# Project_Tsc_v40.net
KiCad netlist of a schematic drawn in EAGLE
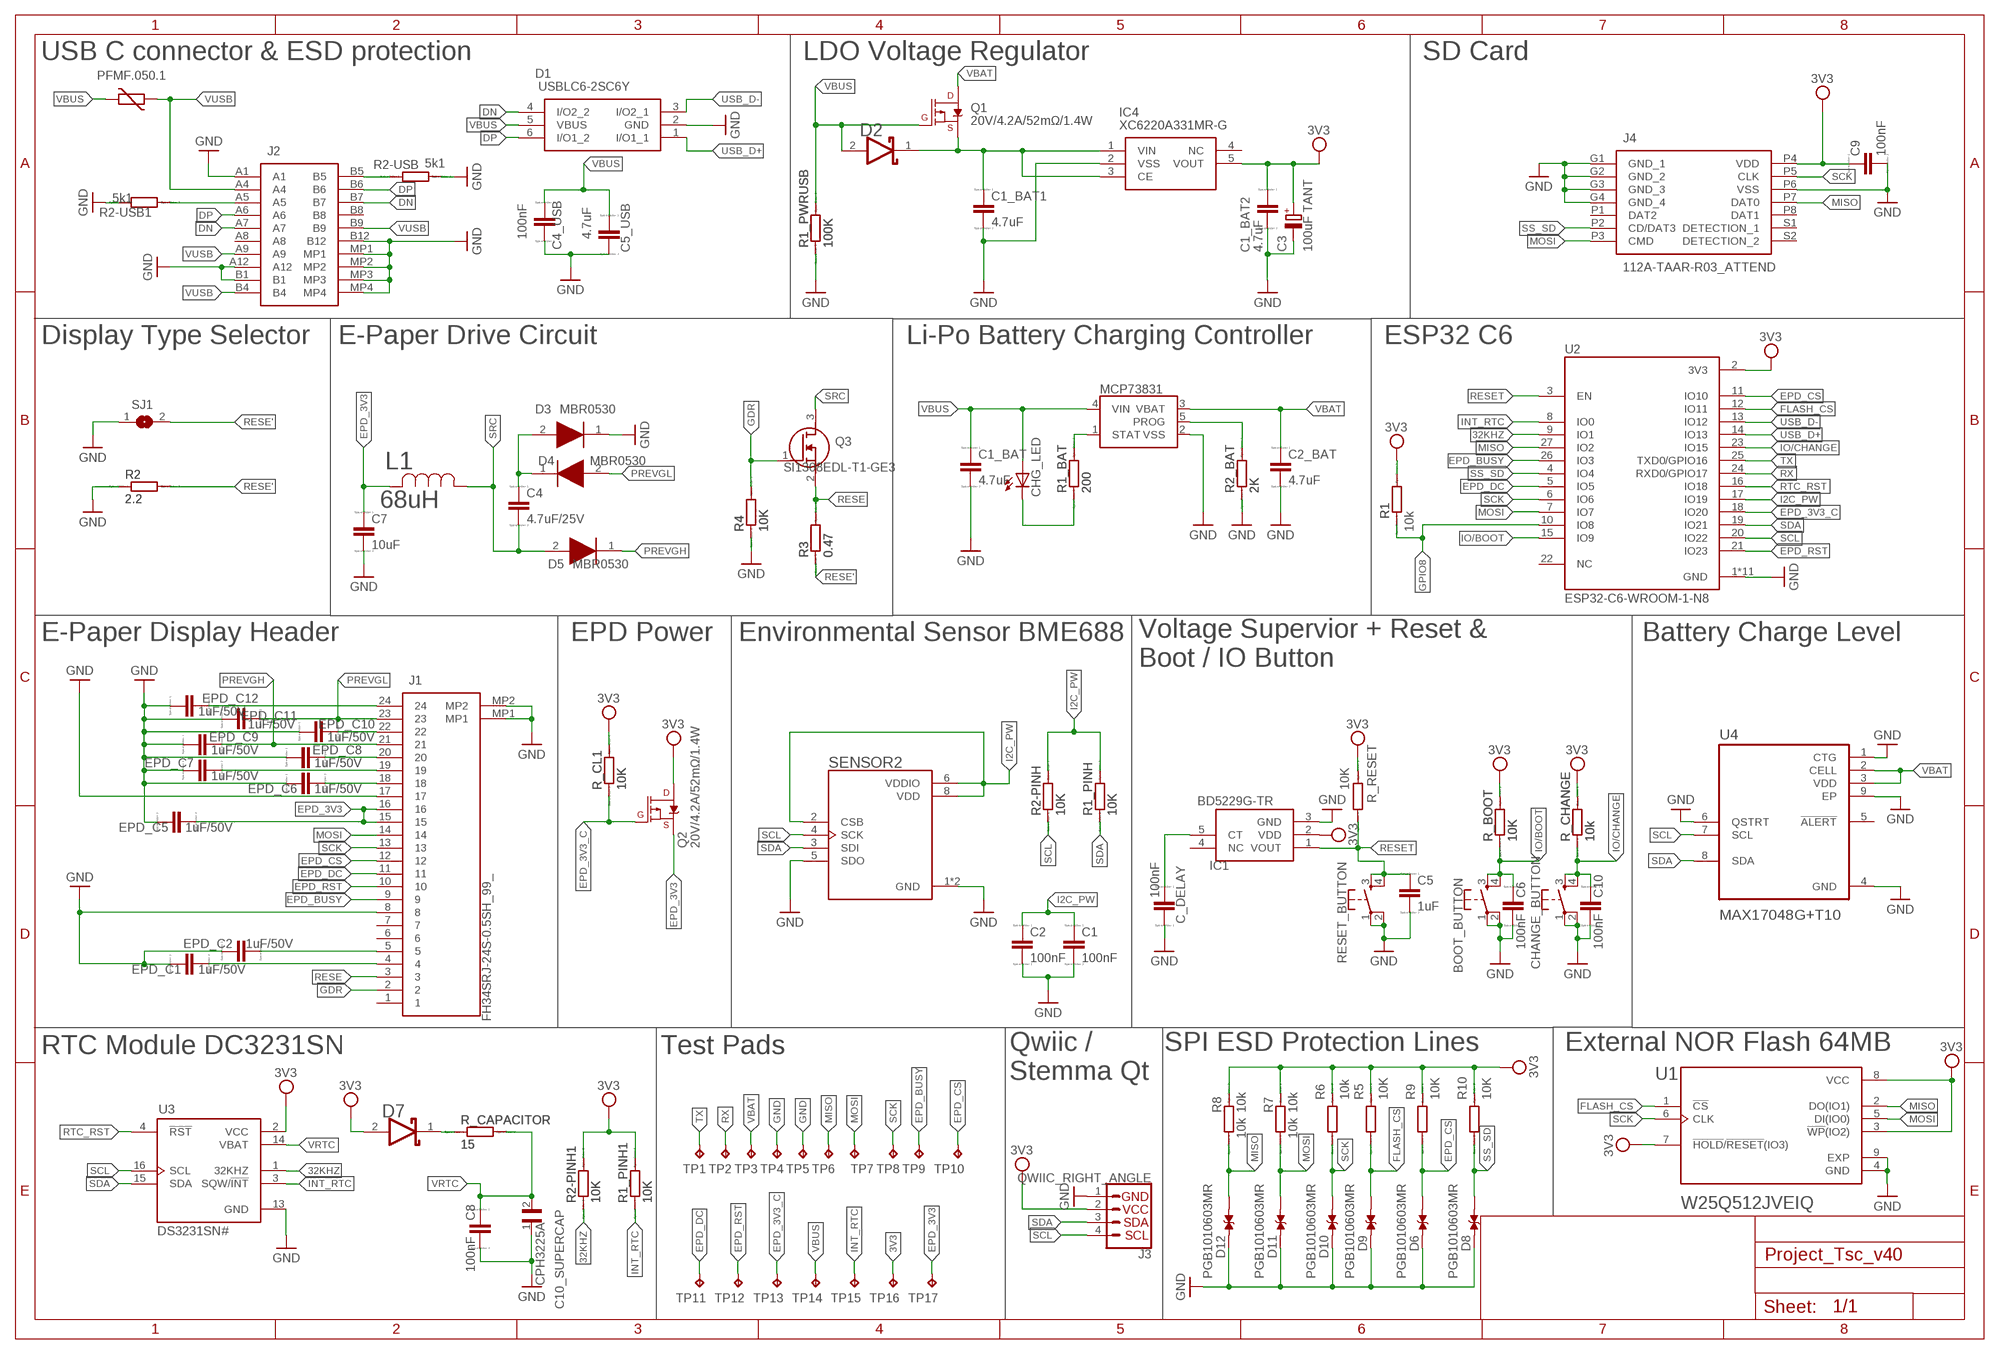
[diagram p0: schematic, sheet 1]

(export (version "E")
  (design (tool "Eeschema 10.0.6"))
  (components
    (comp (ref "BOOT_BUTTON")
      (value "BUTTON_CUSYOMV1")
      (footprint "eagle-import:MYBUTTON")
      (libsource (lib "eagle-import") (part "BUTTON_CUSYOMV1"))
    )
    (comp (ref "C1")
      (value "100nF")
      (footprint "eagle-import:EAGLE-LTSPICE_C0402")
      (libsource (lib "eagle-import") (part "EAGLE-LTSPICE_CC0402"))
    )
    (comp (ref "C1_BAT")
      (value "4.7uF")
      (footprint "eagle-import:ESP32_WROVER_EAGLE-LTSPICE_C0402")
      (libsource (lib "eagle-import") (part "ESP32_WROVER_EAGLE-LTSPICE_CC0402"))
    )
    (comp (ref "C1_BAT1")
      (value "4.7uF")
      (footprint "eagle-import:ESP32_WROVER_EAGLE-LTSPICE_C0402")
      (libsource (lib "eagle-import") (part "ESP32_WROVER_EAGLE-LTSPICE_CC0402"))
    )
    (comp (ref "C1_BAT2")
      (value "4.7uF")
      (footprint "eagle-import:ESP32_WROVER_EAGLE-LTSPICE_C0402")
      (libsource (lib "eagle-import") (part "ESP32_WROVER_EAGLE-LTSPICE_CC0402"))
    )
    (comp (ref "C2")
      (value "100nF")
      (footprint "eagle-import:EAGLE-LTSPICE_C0402")
      (libsource (lib "eagle-import") (part "EAGLE-LTSPICE_CC0402"))
    )
    (comp (ref "C2_BAT")
      (value "4.7uF")
      (footprint "eagle-import:ESP32_WROVER_EAGLE-LTSPICE_C0402")
      (libsource (lib "eagle-import") (part "ESP32_WROVER_EAGLE-LTSPICE_CC0402"))
    )
    (comp (ref "C3")
      (value "100uF TANT")
      (footprint "eagle-import:RCL_CT3528")
      (libsource (lib "eagle-import") (part "RCL_CPOL-EUCT3528"))
    )
    (comp (ref "C4")
      (value "4.7uF/25V")
      (footprint "eagle-import:ESP32_WROVER_EAGLE-LTSPICE_C0402")
      (libsource (lib "eagle-import") (part "ESP32_WROVER_EAGLE-LTSPICE_CC0402"))
    )
    (comp (ref "C4_USB")
      (value "100nF")
      (footprint "eagle-import:ESP32_WROVER_EAGLE-LTSPICE_C0402")
      (libsource (lib "eagle-import") (part "ESP32_WROVER_EAGLE-LTSPICE_CC0402"))
    )
    (comp (ref "C5")
      (value "1uF")
      (footprint "eagle-import:EAGLE-LTSPICE_C0402")
      (libsource (lib "eagle-import") (part "EAGLE-LTSPICE_CC0402"))
    )
    (comp (ref "C5_USB")
      (value "4.7uF")
      (footprint "eagle-import:ESP32_WROVER_EAGLE-LTSPICE_C0402")
      (libsource (lib "eagle-import") (part "ESP32_WROVER_EAGLE-LTSPICE_CC0402"))
    )
    (comp (ref "C6")
      (value "100nF")
      (footprint "eagle-import:EAGLE-LTSPICE_C0402")
      (libsource (lib "eagle-import") (part "EAGLE-LTSPICE_CC0402"))
    )
    (comp (ref "C7")
      (value "10uF")
      (footprint "eagle-import:EAGLE-LTSPICE_C0402")
      (libsource (lib "eagle-import") (part "EAGLE-LTSPICE_CC0402"))
    )
    (comp (ref "C8")
      (value "100nF")
      (footprint "eagle-import:ESP32_WROVER_EAGLE-LTSPICE_C0402")
      (libsource (lib "eagle-import") (part "ESP32_WROVER_EAGLE-LTSPICE_CC0402"))
    )
    (comp (ref "C9")
      (value "100nF")
      (footprint "eagle-import:EAGLE-LTSPICE_C0402")
      (libsource (lib "eagle-import") (part "EAGLE-LTSPICE_CC0402"))
    )
    (comp (ref "C10")
      (value "100nF")
      (footprint "eagle-import:EAGLE-LTSPICE_C0402")
      (libsource (lib "eagle-import") (part "EAGLE-LTSPICE_CC0402"))
    )
    (comp (ref "C10_SUPERCAP")
      (value "CPH3225A")
      (footprint "eagle-import:CAPCP3225X100N")
      (fields (field (name "MF") "Seiko Instruments"))
      (libsource (lib "eagle-import") (part "CPH3225A"))
    )
    (comp (ref "CHANGE_BUTTON")
      (value "BUTTON_CUSYOMV1")
      (footprint "eagle-import:MYBUTTON")
      (libsource (lib "eagle-import") (part "BUTTON_CUSYOMV1"))
    )
    (comp (ref "CHG_LED")
      (value "ADAFRUIT_LEDCHIP-LED0603")
      (footprint "eagle-import:ADAFRUIT_CHIP-LED0603")
      (libsource (lib "eagle-import") (part "ADAFRUIT_LEDCHIP-LED0603"))
    )
    (comp (ref "C_DELAY")
      (value "100nF")
      (footprint "eagle-import:ESP32_WROVER_EAGLE-LTSPICE_C0402")
      (libsource (lib "eagle-import") (part "ESP32_WROVER_EAGLE-LTSPICE_CC0402"))
    )
    (comp (ref "D1")
      (value "USBLC6-2SC6Y")
      (footprint "eagle-import:SOT95P280X145-6N")
      (fields (field (name "MF") "STMicroelectronics"))
      (libsource (lib "eagle-import") (part "USBLC6-2SC6Y"))
    )
    (comp (ref "D2")
      (value "ESP32_WROVER_AVX---SD0805S020S1R0_AVX_SD0805S020S1R0_0_0AVX_SD0805S020S1R0_0_0")
      (footprint "eagle-import:ESP32_WROVER_AVX---SD0805S020S1R0_AVX_SD0805S020S1R0_0")
      (fields
        (field (name "DIGIKEY_PART_NUMBER") "478-7800-1-ND")
        (field (name "MF") "AVX")
        (field (name "MOUSER_PART_NUMBER") "581-SD0805S020S1R0")
      )
      (libsource (lib "eagle-import") (part "ESP32_WROVER_AVX---SD0805S020S1R0_AVX_SD0805S020S1R0_0_0AVX_SD0805S020S1R0_0_0"))
    )
    (comp (ref "D3")
      (value "MBR0530")
      (footprint "eagle-import:SOD3716X135N")
      (fields (field (name "MF") "ON Semiconductor"))
      (libsource (lib "eagle-import") (part "MBR0530"))
    )
    (comp (ref "D4")
      (value "MBR0530")
      (footprint "eagle-import:SOD3716X135N")
      (fields (field (name "MF") "ON Semiconductor"))
      (libsource (lib "eagle-import") (part "MBR0530"))
    )
    (comp (ref "D5")
      (value "MBR0530")
      (footprint "eagle-import:SOD3716X135N")
      (fields (field (name "MF") "ON Semiconductor"))
      (libsource (lib "eagle-import") (part "MBR0530"))
    )
    (comp (ref "D6")
      (value "PGB1010603MR")
      (footprint "eagle-import:DIOC1608X36N")
      (fields (field (name "MF") "Littelfuse Inc."))
      (libsource (lib "eagle-import") (part "PGB1010603MR"))
    )
    (comp (ref "D7")
      (value "ESP32_WROVER_AVX---SD0805S020S1R0_AVX_SD0805S020S1R0_0_0AVX_SD0805S020S1R0_0_0")
      (footprint "eagle-import:ESP32_WROVER_AVX---SD0805S020S1R0_AVX_SD0805S020S1R0_0")
      (fields
        (field (name "DIGIKEY_PART_NUMBER") "478-7800-1-ND")
        (field (name "MF") "AVX")
        (field (name "MOUSER_PART_NUMBER") "581-SD0805S020S1R0")
      )
      (libsource (lib "eagle-import") (part "ESP32_WROVER_AVX---SD0805S020S1R0_AVX_SD0805S020S1R0_0_0AVX_SD0805S020S1R0_0_0"))
    )
    (comp (ref "D8")
      (value "PGB1010603MR")
      (footprint "eagle-import:DIOC1608X36N")
      (fields (field (name "MF") "Littelfuse Inc."))
      (libsource (lib "eagle-import") (part "PGB1010603MR"))
    )
    (comp (ref "D9")
      (value "PGB1010603MR")
      (footprint "eagle-import:DIOC1608X36N")
      (fields (field (name "MF") "Littelfuse Inc."))
      (libsource (lib "eagle-import") (part "PGB1010603MR"))
    )
    (comp (ref "D10")
      (value "PGB1010603MR")
      (footprint "eagle-import:DIOC1608X36N")
      (fields (field (name "MF") "Littelfuse Inc."))
      (libsource (lib "eagle-import") (part "PGB1010603MR"))
    )
    (comp (ref "D11")
      (value "PGB1010603MR")
      (footprint "eagle-import:DIOC1608X36N")
      (fields (field (name "MF") "Littelfuse Inc."))
      (libsource (lib "eagle-import") (part "PGB1010603MR"))
    )
    (comp (ref "D12")
      (value "PGB1010603MR")
      (footprint "eagle-import:DIOC1608X36N")
      (fields (field (name "MF") "Littelfuse Inc."))
      (libsource (lib "eagle-import") (part "PGB1010603MR"))
    )
    (comp (ref "EPD_C1")
      (value "1uF/50V")
      (footprint "eagle-import:EAGLE-LTSPICE_C0402")
      (libsource (lib "eagle-import") (part "EAGLE-LTSPICE_CC0402"))
    )
    (comp (ref "EPD_C2")
      (value "1uF/50V")
      (footprint "eagle-import:EAGLE-LTSPICE_C0402")
      (libsource (lib "eagle-import") (part "EAGLE-LTSPICE_CC0402"))
    )
    (comp (ref "EPD_C5")
      (value "1uF/50V")
      (footprint "eagle-import:EAGLE-LTSPICE_C0402")
      (libsource (lib "eagle-import") (part "EAGLE-LTSPICE_CC0402"))
    )
    (comp (ref "EPD_C6")
      (value "1uF/50V")
      (footprint "eagle-import:EAGLE-LTSPICE_C0402")
      (libsource (lib "eagle-import") (part "EAGLE-LTSPICE_CC0402"))
    )
    (comp (ref "EPD_C7")
      (value "1uF/50V")
      (footprint "eagle-import:EAGLE-LTSPICE_C0402")
      (libsource (lib "eagle-import") (part "EAGLE-LTSPICE_CC0402"))
    )
    (comp (ref "EPD_C8")
      (value "1uF/50V")
      (footprint "eagle-import:EAGLE-LTSPICE_C0402")
      (libsource (lib "eagle-import") (part "EAGLE-LTSPICE_CC0402"))
    )
    (comp (ref "EPD_C9")
      (value "1uF/50V")
      (footprint "eagle-import:EAGLE-LTSPICE_C0402")
      (libsource (lib "eagle-import") (part "EAGLE-LTSPICE_CC0402"))
    )
    (comp (ref "EPD_C10")
      (value "1uF/50V")
      (footprint "eagle-import:EAGLE-LTSPICE_C0402")
      (libsource (lib "eagle-import") (part "EAGLE-LTSPICE_CC0402"))
    )
    (comp (ref "EPD_C11")
      (value "1uF/50V")
      (footprint "eagle-import:EAGLE-LTSPICE_C0402")
      (libsource (lib "eagle-import") (part "EAGLE-LTSPICE_CC0402"))
    )
    (comp (ref "EPD_C12")
      (value "1uF/50V")
      (footprint "eagle-import:EAGLE-LTSPICE_C0402")
      (libsource (lib "eagle-import") (part "EAGLE-LTSPICE_CC0402"))
    )
    (comp (ref "IC1")
      (value "BD5229G-TR")
      (footprint "eagle-import:SOT95P280X125-5N")
      (fields (field (name "MOUSER_PART_NUMBER") "755-BD5229G-TR"))
      (libsource (lib "eagle-import") (part "BD5229G-TR"))
    )
    (comp (ref "IC4")
      (value "XC6220A331MR-G")
      (footprint "eagle-import:SOT95P280X120-5N")
      (fields (field (name "MOUSER_PART_NUMBER") "865-XC6220A331MR-G"))
      (libsource (lib "eagle-import") (part "XC6220A331MR-G"))
    )
    (comp (ref "J1")
      (value "FH34SRJ-24S-0.5SH_99_")
      (footprint "eagle-import:FH34SRJ24S05SH99")
      (fields
        (field (name "MANUFACTURER_PART_NUMBER") "FH34SRJ-24S-0.5SH(99)")
        (field (name "MOUSER_PART_NUMBER") "798-FH34SRJ24S05SH99")
      )
      (libsource (lib "eagle-import") (part "FH34SRJ-24S-0.5SH_99_"))
    )
    (comp (ref "J2")
      (value "SAMACSYS_PARTS_USB4110-GF-A")
      (footprint "eagle-import:SAMACSYS_PARTS_USB4110GFA")
      (fields
        (field (name "MANUFACTURER_PART_NUMBER") "USB4110-GF-A")
        (field (name "MOUSER_PART_NUMBER") "640-USB4110-GF-A")
      )
      (libsource (lib "eagle-import") (part "SAMACSYS_PARTS_USB4110-GF-A"))
    )
    (comp (ref "J3")
      (value "QWIIC_RIGHT_ANGLE")
      (footprint "eagle-import:JST04_1MM_RA")
      (libsource (lib "eagle-import") (part "QWIIC_CONNECTORJS-1MM"))
    )
    (comp (ref "J4")
      (value "112A-TAAR-R03_ATTEND")
      (footprint "eagle-import:112ATAARR03ATTEND")
      (fields (field (name "MANUFACTURER_PART_NUMBER") "112A-TAAR-R03 ATTEND"))
      (libsource (lib "eagle-import") (part "112A-TAAR-R03_ATTEND"))
    )
    (comp (ref "L1")
      (value "68uH")
      (footprint "eagle-import:IND_4828-WE-TPC_WRE")
      (fields
        (field (name "MANUFACTURER_PART_NUMBER") "744043680")
        (field (name "COPYRIGHT") "Copyright (C) 2024 Ultra Librarian. All rights reserved.")
      )
      (libsource (lib "eagle-import") (part "744043680IND_4828-WE-TPC_WRE"))
    )
    (comp (ref "MCP73831")
      (value "ESP32_WROVER_SPARKFUN-IC-POWER_MCP73831")
      (footprint "eagle-import:ESP32_WROVER_SPARKFUN-IC-POWER_SOT23-5")
      (libsource (lib "eagle-import") (part "ESP32_WROVER_SPARKFUN-IC-POWER_MCP73831"))
    )
    (comp (ref "PFMF.050.1")
      (value "ESP32C6_VARISTORCN1812")
      (footprint "eagle-import:ESP32C6_VARISTOR_CT_CN1812")
      (libsource (lib "eagle-import") (part "ESP32C6_VARISTORCN1812"))
    )
    (comp (ref "Q1")
      (value "20V/4.2A/52mΩ/1.4W")
      (footprint "eagle-import:ESP32_WROVER_SPARKFUN-DISCRETESEMI_SOT23-3")
      (libsource (lib "eagle-import") (part "ESP32_WROVER_SPARKFUN-DISCRETESEMI_MOSFET_PCH-DMG2305UX-7"))
    )
    (comp (ref "Q2")
      (value "20V/4.2A/52mΩ/1.4W")
      (footprint "eagle-import:ESP32_WROVER_SPARKFUN-DISCRETESEMI_SOT23-3")
      (libsource (lib "eagle-import") (part "ESP32_WROVER_SPARKFUN-DISCRETESEMI_MOSFET_PCH-DMG2305UX-7"))
    )
    (comp (ref "Q3")
      (value "SI1308EDL-T1-GE3")
      (footprint "eagle-import:SOT65P210X110-3N")
      (fields (field (name "MF") "Vishay Siliconix"))
      (libsource (lib "eagle-import") (part "SI1308EDL-T1-GE3"))
    )
    (comp (ref "R1")
      (value "10k")
      (footprint "eagle-import:ESP32_WROVER_EAGLE-LTSPICE_R0402")
      (libsource (lib "eagle-import") (part "ESP32_WROVER_EAGLE-LTSPICE_RR0402"))
    )
    (comp (ref "R1_BAT")
      (value "200")
      (footprint "eagle-import:ESP32_WROVER_EAGLE-LTSPICE_R0402")
      (libsource (lib "eagle-import") (part "ESP32_WROVER_EAGLE-LTSPICE_RR0402"))
    )
    (comp (ref "R1_PINH")
      (value "10K")
      (footprint "eagle-import:ESP32_WROVER_EAGLE-LTSPICE_R0402")
      (libsource (lib "eagle-import") (part "ESP32_WROVER_EAGLE-LTSPICE_RR0402"))
    )
    (comp (ref "R1_PINH1")
      (value "10K")
      (footprint "eagle-import:ESP32_WROVER_EAGLE-LTSPICE_R0402")
      (libsource (lib "eagle-import") (part "ESP32_WROVER_EAGLE-LTSPICE_RR0402"))
    )
    (comp (ref "R1_PWRUSB")
      (value "100K")
      (footprint "eagle-import:ESP32_WROVER_EAGLE-LTSPICE_R0402")
      (libsource (lib "eagle-import") (part "ESP32_WROVER_EAGLE-LTSPICE_RR0402"))
    )
    (comp (ref "R2")
      (value "2.2")
      (footprint "eagle-import:ESP32_WROVER_EAGLE-LTSPICE_R0402")
      (libsource (lib "eagle-import") (part "ESP32_WROVER_EAGLE-LTSPICE_RR0402"))
    )
    (comp (ref "R2-PINH")
      (value "10K")
      (footprint "eagle-import:ESP32_WROVER_EAGLE-LTSPICE_R0402")
      (libsource (lib "eagle-import") (part "ESP32_WROVER_EAGLE-LTSPICE_RR0402"))
    )
    (comp (ref "R2-PINH1")
      (value "10K")
      (footprint "eagle-import:ESP32_WROVER_EAGLE-LTSPICE_R0402")
      (libsource (lib "eagle-import") (part "ESP32_WROVER_EAGLE-LTSPICE_RR0402"))
    )
    (comp (ref "R2-USB")
      (value "5k1")
      (footprint "eagle-import:ESP32_WROVER_EAGLE-LTSPICE_R0402")
      (libsource (lib "eagle-import") (part "ESP32_WROVER_EAGLE-LTSPICE_RR0402"))
    )
    (comp (ref "R2-USB1")
      (value "5k1")
      (footprint "eagle-import:ESP32_WROVER_EAGLE-LTSPICE_R0402")
      (libsource (lib "eagle-import") (part "ESP32_WROVER_EAGLE-LTSPICE_RR0402"))
    )
    (comp (ref "R2_BAT")
      (value "2K")
      (footprint "eagle-import:ESP32_WROVER_EAGLE-LTSPICE_R0402")
      (libsource (lib "eagle-import") (part "ESP32_WROVER_EAGLE-LTSPICE_RR0402"))
    )
    (comp (ref "R3")
      (value "0.47")
      (footprint "eagle-import:ESP32_WROVER_EAGLE-LTSPICE_R0402")
      (libsource (lib "eagle-import") (part "ESP32_WROVER_EAGLE-LTSPICE_RR0402"))
    )
    (comp (ref "R4")
      (value "10K")
      (footprint "eagle-import:ESP32_WROVER_EAGLE-LTSPICE_R0402")
      (libsource (lib "eagle-import") (part "ESP32_WROVER_EAGLE-LTSPICE_RR0402"))
    )
    (comp (ref "R5")
      (value "10K")
      (footprint "eagle-import:ESP32_WROVER_EAGLE-LTSPICE_R0402")
      (libsource (lib "eagle-import") (part "ESP32_WROVER_EAGLE-LTSPICE_RR0402"))
    )
    (comp (ref "R6")
      (value "10k")
      (footprint "eagle-import:ESP32_WROVER_EAGLE-LTSPICE_R0402")
      (libsource (lib "eagle-import") (part "ESP32_WROVER_EAGLE-LTSPICE_RR0402"))
    )
    (comp (ref "R7")
      (value "10k")
      (footprint "eagle-import:ESP32_WROVER_EAGLE-LTSPICE_R0402")
      (libsource (lib "eagle-import") (part "ESP32_WROVER_EAGLE-LTSPICE_RR0402"))
    )
    (comp (ref "R8")
      (value "10k")
      (footprint "eagle-import:ESP32_WROVER_EAGLE-LTSPICE_R0402")
      (libsource (lib "eagle-import") (part "ESP32_WROVER_EAGLE-LTSPICE_RR0402"))
    )
    (comp (ref "R9")
      (value "10K")
      (footprint "eagle-import:ESP32_WROVER_EAGLE-LTSPICE_R0402")
      (libsource (lib "eagle-import") (part "ESP32_WROVER_EAGLE-LTSPICE_RR0402"))
    )
    (comp (ref "R10")
      (value "10K")
      (footprint "eagle-import:ESP32_WROVER_EAGLE-LTSPICE_R0402")
      (libsource (lib "eagle-import") (part "ESP32_WROVER_EAGLE-LTSPICE_RR0402"))
    )
    (comp (ref "RESET_BUTTON")
      (value "BUTTON_CUSYOMV1")
      (footprint "eagle-import:MYBUTTON")
      (libsource (lib "eagle-import") (part "BUTTON_CUSYOMV1"))
    )
    (comp (ref "R_BOOT")
      (value "10K")
      (footprint "eagle-import:ESP32_WROVER_EAGLE-LTSPICE_R0402")
      (libsource (lib "eagle-import") (part "ESP32_WROVER_EAGLE-LTSPICE_RR0402"))
    )
    (comp (ref "R_CAPACITOR")
      (value "15")
      (footprint "eagle-import:ESP32_WROVER_EAGLE-LTSPICE_R0402")
      (libsource (lib "eagle-import") (part "ESP32_WROVER_EAGLE-LTSPICE_RR0402"))
    )
    (comp (ref "R_CHANGE")
      (value "10k")
      (footprint "eagle-import:ESP32_WROVER_EAGLE-LTSPICE_R0402")
      (libsource (lib "eagle-import") (part "ESP32_WROVER_EAGLE-LTSPICE_RR0402"))
    )
    (comp (ref "R_CL1")
      (value "10K")
      (footprint "eagle-import:ESP32_WROVER_EAGLE-LTSPICE_R0402")
      (libsource (lib "eagle-import") (part "ESP32_WROVER_EAGLE-LTSPICE_RR0402"))
    )
    (comp (ref "R_RESET")
      (value "10K")
      (footprint "eagle-import:ESP32_WROVER_EAGLE-LTSPICE_R0402")
      (libsource (lib "eagle-import") (part "ESP32_WROVER_EAGLE-LTSPICE_RR0402"))
    )
    (comp (ref "SENSOR2")
      (value "ESP32_WROVER_BME680_BME680")
      (footprint "eagle-import:ESP32_WROVER_BME680_PSON80P300X300X100-8N")
      (fields (field (name "MF") "Bosch Sensortec") (field (name "MP") "BME680"))
      (libsource (lib "eagle-import") (part "ESP32_WROVER_BME680_BME680"))
    )
    (comp (ref "SJ1") (value "SJ") (footprint "eagle-import:SJ") (libsource (lib "eagle-import") (part "SJ")))
    (comp (ref "TP1")
      (value "TPTP20R")
      (footprint "eagle-import:TP20R")
      (libsource (lib "eagle-import") (part "TPTP20R"))
    )
    (comp (ref "TP2")
      (value "TPTP20R")
      (footprint "eagle-import:TP20R")
      (libsource (lib "eagle-import") (part "TPTP20R"))
    )
    (comp (ref "TP3")
      (value "TPTP20R")
      (footprint "eagle-import:TP20R")
      (libsource (lib "eagle-import") (part "TPTP20R"))
    )
    (comp (ref "TP4")
      (value "TPTP20R")
      (footprint "eagle-import:TP20R")
      (libsource (lib "eagle-import") (part "TPTP20R"))
    )
    (comp (ref "TP5")
      (value "TPTP20R")
      (footprint "eagle-import:TP20R")
      (libsource (lib "eagle-import") (part "TPTP20R"))
    )
    (comp (ref "TP6")
      (value "TPTP20R")
      (footprint "eagle-import:TP20R")
      (libsource (lib "eagle-import") (part "TPTP20R"))
    )
    (comp (ref "TP7")
      (value "TPTP20R")
      (footprint "eagle-import:TP20R")
      (libsource (lib "eagle-import") (part "TPTP20R"))
    )
    (comp (ref "TP8")
      (value "TPTP20R")
      (footprint "eagle-import:TP20R")
      (libsource (lib "eagle-import") (part "TPTP20R"))
    )
    (comp (ref "TP9")
      (value "TPTP20R")
      (footprint "eagle-import:TP20R")
      (libsource (lib "eagle-import") (part "TPTP20R"))
    )
    (comp (ref "TP10")
      (value "TPTP20R")
      (footprint "eagle-import:TP20R")
      (libsource (lib "eagle-import") (part "TPTP20R"))
    )
    (comp (ref "TP11")
      (value "TPTP20R")
      (footprint "eagle-import:TP20R")
      (libsource (lib "eagle-import") (part "TPTP20R"))
    )
    (comp (ref "TP12")
      (value "TPTP20R")
      (footprint "eagle-import:TP20R")
      (libsource (lib "eagle-import") (part "TPTP20R"))
    )
    (comp (ref "TP13")
      (value "TPTP20R")
      (footprint "eagle-import:TP20R")
      (libsource (lib "eagle-import") (part "TPTP20R"))
    )
    (comp (ref "TP14")
      (value "TPTP20R")
      (footprint "eagle-import:TP20R")
      (libsource (lib "eagle-import") (part "TPTP20R"))
    )
    (comp (ref "TP15")
      (value "TPTP20R")
      (footprint "eagle-import:TP20R")
      (libsource (lib "eagle-import") (part "TPTP20R"))
    )
    (comp (ref "TP16")
      (value "TPTP20R")
      (footprint "eagle-import:TP20R")
      (libsource (lib "eagle-import") (part "TPTP20R"))
    )
    (comp (ref "TP17")
      (value "TPTP20R")
      (footprint "eagle-import:TP20R")
      (libsource (lib "eagle-import") (part "TPTP20R"))
    )
    (comp (ref "U1")
      (value "W25Q512JVEIQ")
      (footprint "eagle-import:SON127P600X800X80-9N")
      (fields (field (name "MF") "Winbond Electronics"))
      (libsource (lib "eagle-import") (part "W25Q512JVEIQ"))
    )
    (comp (ref "U2")
      (value "ESP32-C6-WROOM-1-N8")
      (footprint "eagle-import:XCVR_ESP32-C6-WROOM-1-N8")
      (fields (field (name "MF") "Espressif Systems"))
      (libsource (lib "eagle-import") (part "ESP32-C6-WROOM-1-N8"))
    )
    (comp (ref "U3")
      (value "DS3231SN#")
      (footprint "eagle-import:SOIC127P1032X265-16N")
      (fields (field (name "MF") "Analog Devices"))
      (libsource (lib "eagle-import") (part "DS3231SN#"))
    )
    (comp (ref "U4")
      (value "MAX17048G+T10")
      (footprint "eagle-import:SON50P200X200X80-9N")
      (fields (field (name "MF") "Analog Devices"))
      (libsource (lib "eagle-import") (part "MAX17048G+T10"))
    )
  )
  (nets
    (net (code "1") (name "3V3") (class "Default")
      (node (ref "C1_BAT2") (pin "1") (pinfunction "1_1") (pintype "passive"))
      (node (ref "C3") (pin "+") (pinfunction "+_+") (pintype "passive"))
      (node (ref "C9") (pin "1") (pinfunction "1_1") (pintype "passive"))
      (node (ref "D7") (pin "2") (pinfunction "ANODE_2") (pintype "bidirectional"))
      (node (ref "IC1") (pin "2") (pinfunction "VDD_2") (pintype "bidirectional"))
      (node (ref "IC4") (pin "5") (pinfunction "VOUT_5") (pintype "bidirectional"))
      (node (ref "J3") (pin "2") (pinfunction "2_2") (pintype "power_in"))
      (node (ref "J4") (pin "P4") (pinfunction "VDD_P4") (pintype "bidirectional"))
      (node (ref "Q2") (pin "3") (pinfunction "D_3") (pintype "bidirectional"))
      (node (ref "R1") (pin "2") (pinfunction "2_2") (pintype "passive"))
      (node (ref "R10") (pin "2") (pinfunction "2_2") (pintype "passive"))
      (node (ref "R1_PINH1") (pin "2") (pinfunction "2_2") (pintype "passive"))
      (node (ref "R2-PINH1") (pin "2") (pinfunction "2_2") (pintype "passive"))
      (node (ref "R5") (pin "2") (pinfunction "2_2") (pintype "passive"))
      (node (ref "R6") (pin "2") (pinfunction "2_2") (pintype "passive"))
      (node (ref "R7") (pin "2") (pinfunction "2_2") (pintype "passive"))
      (node (ref "R8") (pin "2") (pinfunction "2_2") (pintype "passive"))
      (node (ref "R9") (pin "2") (pinfunction "2_2") (pintype "passive"))
      (node (ref "R_BOOT") (pin "2") (pinfunction "2_2") (pintype "passive"))
      (node (ref "R_CHANGE") (pin "2") (pinfunction "2_2") (pintype "passive"))
      (node (ref "R_CL1") (pin "2") (pinfunction "2_2") (pintype "passive"))
      (node (ref "R_RESET") (pin "2") (pinfunction "2_2") (pintype "passive"))
      (node (ref "TP16") (pin "TP") (pinfunction "TP_TP") (pintype "input"))
      (node (ref "U1") (pin "3") (pinfunction "~{WP}(IO2)_3") (pintype "bidirectional"))
      (node (ref "U1") (pin "7") (pinfunction "~{HOLD}/~{RESET}(IO3)_7") (pintype "bidirectional"))
      (node (ref "U1") (pin "8") (pinfunction "VCC_8") (pintype "power_in"))
      (node (ref "U2") (pin "2") (pinfunction "3V3_2") (pintype "power_in"))
      (node (ref "U3") (pin "2") (pinfunction "VCC_2") (pintype "power_in"))
    )
    (net (code "2") (name "32KHZ") (class "Default")
      (node (ref "R2-PINH1") (pin "1") (pinfunction "1_1") (pintype "passive"))
      (node (ref "U2") (pin "9") (pinfunction "IO1_9") (pintype "bidirectional"))
      (node (ref "U3") (pin "1") (pinfunction "32KHZ_1") (pintype "output"))
    )
    (net (code "3") (name "DN") (class "Default")
      (node (ref "D1") (pin "4") (pinfunction "I/O2_2_4") (pintype "bidirectional"))
      (node (ref "J2") (pin "A7") (pinfunction "A7_A7") (pintype "bidirectional"))
      (node (ref "J2") (pin "B7") (pinfunction "B7_B7") (pintype "bidirectional"))
    )
    (net (code "4") (name "DP") (class "Default")
      (node (ref "D1") (pin "6") (pinfunction "I/O1_2_6") (pintype "bidirectional"))
      (node (ref "J2") (pin "A6") (pinfunction "A6_A6") (pintype "bidirectional"))
      (node (ref "J2") (pin "B6") (pinfunction "B6_B6") (pintype "bidirectional"))
    )
    (net (code "5") (name "EPD_3V3") (class "Default")
      (node (ref "C7") (pin "1") (pinfunction "1_1") (pintype "passive"))
      (node (ref "EPD_C5") (pin "2") (pinfunction "2_2") (pintype "passive"))
      (node (ref "J1") (pin "15") (pinfunction "15_15") (pintype "bidirectional"))
      (node (ref "J1") (pin "16") (pinfunction "16_16") (pintype "bidirectional"))
      (node (ref "L1") (pin "2") (pinfunction "2_2") (pintype "passive"))
      (node (ref "Q2") (pin "2") (pinfunction "S_2") (pintype "bidirectional"))
      (node (ref "TP17") (pin "TP") (pinfunction "TP_TP") (pintype "input"))
    )
    (net (code "6") (name "EPD_3V3_C") (class "Default")
      (node (ref "Q2") (pin "1") (pinfunction "G_1") (pintype "bidirectional"))
      (node (ref "R_CL1") (pin "1") (pinfunction "1_1") (pintype "passive"))
      (node (ref "TP13") (pin "TP") (pinfunction "TP_TP") (pintype "input"))
      (node (ref "U2") (pin "18") (pinfunction "IO20_18") (pintype "bidirectional"))
    )
    (net (code "7") (name "EPD_BUSY") (class "Default")
      (node (ref "J1") (pin "9") (pinfunction "9_9") (pintype "bidirectional"))
      (node (ref "TP9") (pin "TP") (pinfunction "TP_TP") (pintype "input"))
      (node (ref "U2") (pin "26") (pinfunction "IO3_26") (pintype "bidirectional"))
    )
    (net (code "8") (name "EPD_CS") (class "Default")
      (node (ref "D6") (pin "1") (pinfunction "1_1") (pintype "passive"))
      (node (ref "J1") (pin "12") (pinfunction "12_12") (pintype "bidirectional"))
      (node (ref "R9") (pin "1") (pinfunction "1_1") (pintype "passive"))
      (node (ref "TP10") (pin "TP") (pinfunction "TP_TP") (pintype "input"))
      (node (ref "U2") (pin "11") (pinfunction "IO10_11") (pintype "bidirectional"))
    )
    (net (code "9") (name "EPD_DC") (class "Default")
      (node (ref "J1") (pin "11") (pinfunction "11_11") (pintype "bidirectional"))
      (node (ref "TP11") (pin "TP") (pinfunction "TP_TP") (pintype "input"))
      (node (ref "U2") (pin "5") (pinfunction "IO5_5") (pintype "bidirectional"))
    )
    (net (code "10") (name "EPD_RST") (class "Default")
      (node (ref "J1") (pin "10") (pinfunction "10_10") (pintype "bidirectional"))
      (node (ref "TP12") (pin "TP") (pinfunction "TP_TP") (pintype "input"))
      (node (ref "U2") (pin "21") (pinfunction "IO23_21") (pintype "bidirectional"))
    )
    (net (code "11") (name "FLASH_CS") (class "Default")
      (node (ref "D9") (pin "1") (pinfunction "1_1") (pintype "passive"))
      (node (ref "R5") (pin "1") (pinfunction "1_1") (pintype "passive"))
      (node (ref "U1") (pin "1") (pinfunction "~{CS}_1") (pintype "input"))
      (node (ref "U2") (pin "12") (pinfunction "IO11_12") (pintype "bidirectional"))
    )
    (net (code "12") (name "GDR") (class "Default")
      (node (ref "J1") (pin "2") (pinfunction "2_2") (pintype "bidirectional"))
      (node (ref "Q3") (pin "1") (pinfunction "G_1") (pintype "bidirectional"))
      (node (ref "R4") (pin "2") (pinfunction "2_2") (pintype "passive"))
    )
    (net (code "13") (name "GND") (class "Default")
      (node (ref "BOOT_BUTTON") (pin "1") (pinfunction "1_1") (pintype "passive"))
      (node (ref "BOOT_BUTTON") (pin "2") (pinfunction "2_2") (pintype "passive"))
      (node (ref "C1") (pin "2") (pinfunction "2_2") (pintype "passive"))
      (node (ref "C10") (pin "2") (pinfunction "2_2") (pintype "passive"))
      (node (ref "C10_SUPERCAP") (pin "1") (pinfunction "1_1") (pintype "passive"))
      (node (ref "C1_BAT") (pin "2") (pinfunction "2_2") (pintype "passive"))
      (node (ref "C1_BAT1") (pin "2") (pinfunction "2_2") (pintype "passive"))
      (node (ref "C1_BAT2") (pin "2") (pinfunction "2_2") (pintype "passive"))
      (node (ref "C2") (pin "2") (pinfunction "2_2") (pintype "passive"))
      (node (ref "C2_BAT") (pin "2") (pinfunction "2_2") (pintype "passive"))
      (node (ref "C3") (pin "-") (pinfunction "-_-") (pintype "passive"))
      (node (ref "C4_USB") (pin "2") (pinfunction "2_2") (pintype "passive"))
      (node (ref "C5") (pin "2") (pinfunction "2_2") (pintype "passive"))
      (node (ref "C5_USB") (pin "2") (pinfunction "2_2") (pintype "passive"))
      (node (ref "C6") (pin "2") (pinfunction "2_2") (pintype "passive"))
      (node (ref "C7") (pin "2") (pinfunction "2_2") (pintype "passive"))
      (node (ref "C8") (pin "2") (pinfunction "2_2") (pintype "passive"))
      (node (ref "C9") (pin "2") (pinfunction "2_2") (pintype "passive"))
      (node (ref "CHANGE_BUTTON") (pin "1") (pinfunction "1_1") (pintype "passive"))
      (node (ref "CHANGE_BUTTON") (pin "2") (pinfunction "2_2") (pintype "passive"))
      (node (ref "C_DELAY") (pin "2") (pinfunction "2_2") (pintype "passive"))
      (node (ref "D1") (pin "2") (pinfunction "GND_2") (pintype "bidirectional"))
      (node (ref "D10") (pin "2") (pinfunction "2_2") (pintype "passive"))
      (node (ref "D11") (pin "2") (pinfunction "2_2") (pintype "passive"))
      (node (ref "D12") (pin "2") (pinfunction "2_2") (pintype "passive"))
      (node (ref "D3") (pin "1") (pinfunction "K_1") (pintype "bidirectional"))
      (node (ref "D6") (pin "2") (pinfunction "2_2") (pintype "passive"))
      (node (ref "D8") (pin "2") (pinfunction "2_2") (pintype "passive"))
      (node (ref "D9") (pin "2") (pinfunction "2_2") (pintype "passive"))
      (node (ref "EPD_C1") (pin "1") (pinfunction "1_1") (pintype "passive"))
      (node (ref "EPD_C10") (pin "1") (pinfunction "1_1") (pintype "passive"))
      (node (ref "EPD_C11") (pin "1") (pinfunction "1_1") (pintype "passive"))
      (node (ref "EPD_C12") (pin "1") (pinfunction "1_1") (pintype "passive"))
      (node (ref "EPD_C2") (pin "1") (pinfunction "1_1") (pintype "passive"))
      (node (ref "EPD_C5") (pin "1") (pinfunction "1_1") (pintype "passive"))
      (node (ref "EPD_C6") (pin "1") (pinfunction "1_1") (pintype "passive"))
      (node (ref "EPD_C7") (pin "1") (pinfunction "1_1") (pintype "passive"))
      (node (ref "EPD_C8") (pin "1") (pinfunction "1_1") (pintype "passive"))
      (node (ref "EPD_C9") (pin "1") (pinfunction "1_1") (pintype "passive"))
      (node (ref "IC1") (pin "3") (pinfunction "GND_3") (pintype "bidirectional"))
      (node (ref "IC4") (pin "2") (pinfunction "VSS_2") (pintype "bidirectional"))
      (node (ref "J1") (pin "17") (pinfunction "17_17") (pintype "bidirectional"))
      (node (ref "J1") (pin "8") (pinfunction "8_8") (pintype "bidirectional"))
      (node (ref "J1") (pin "MP1") (pinfunction "MP1_MP1") (pintype "bidirectional"))
      (node (ref "J1") (pin "MP2") (pinfunction "MP2_MP2") (pintype "bidirectional"))
      (node (ref "J2") (pin "A1") (pinfunction "A1_A1") (pintype "bidirectional"))
      (node (ref "J2") (pin "A12") (pinfunction "A12_A12") (pintype "bidirectional"))
      (node (ref "J2") (pin "B1") (pinfunction "B1_B1") (pintype "bidirectional"))
      (node (ref "J2") (pin "B12") (pinfunction "B12_B12") (pintype "bidirectional"))
      (node (ref "J2") (pin "MP1") (pinfunction "MP1_MP1") (pintype "bidirectional"))
      (node (ref "J2") (pin "MP2") (pinfunction "MP2_MP2") (pintype "bidirectional"))
      (node (ref "J2") (pin "MP3") (pinfunction "MP3_MP3") (pintype "bidirectional"))
      (node (ref "J2") (pin "MP4") (pinfunction "MP4_MP4") (pintype "bidirectional"))
      (node (ref "J3") (pin "1") (pinfunction "1_1") (pintype "power_in"))
      (node (ref "J4") (pin "G1") (pinfunction "GND_1_G1") (pintype "bidirectional"))
      (node (ref "J4") (pin "G2") (pinfunction "GND_2_G2") (pintype "bidirectional"))
      (node (ref "J4") (pin "G3") (pinfunction "GND_3_G3") (pintype "bidirectional"))
      (node (ref "J4") (pin "G4") (pinfunction "GND_4_G4") (pintype "bidirectional"))
      (node (ref "J4") (pin "P6") (pinfunction "VSS_P6") (pintype "bidirectional"))
      (node (ref "MCP73831") (pin "2") (pinfunction "VSS_2") (pintype "power_in"))
      (node (ref "R1_PWRUSB") (pin "1") (pinfunction "1_1") (pintype "passive"))
      (node (ref "R2") (pin "1") (pinfunction "1_1") (pintype "passive"))
      (node (ref "R2-USB") (pin "2") (pinfunction "2_2") (pintype "passive"))
      (node (ref "R2-USB1") (pin "1") (pinfunction "1_1") (pintype "passive"))
      (node (ref "R2_BAT") (pin "1") (pinfunction "1_1") (pintype "passive"))
      (node (ref "R4") (pin "1") (pinfunction "1_1") (pintype "passive"))
      (node (ref "RESET_BUTTON") (pin "1") (pinfunction "1_1") (pintype "passive"))
      (node (ref "RESET_BUTTON") (pin "2") (pinfunction "2_2") (pintype "passive"))
      (node (ref "SENSOR2") (pin "1") (pinfunction "GND_1") (pintype "power_in"))
      (node (ref "SENSOR2") (pin "5") (pinfunction "SDO_5") (pintype "bidirectional"))
      (node (ref "SENSOR2") (pin "7") (pinfunction "GND_7") (pintype "power_in"))
      (node (ref "SJ1") (pin "1") (pinfunction "1_1") (pintype "passive"))
      (node (ref "TP4") (pin "TP") (pinfunction "TP_TP") (pintype "input"))
      (node (ref "TP5") (pin "TP") (pinfunction "TP_TP") (pintype "input"))
      (node (ref "U1") (pin "4") (pinfunction "GND_4") (pintype "power_in"))
      (node (ref "U1") (pin "9") (pinfunction "EXP_9") (pintype "passive"))
      (node (ref "U2") (pin "1") (pinfunction "GND_1") (pintype "power_in"))
      (node (ref "U2") (pin "28") (pinfunction "GND_28") (pintype "power_in"))
      (node (ref "U2") (pin "29_1") (pinfunction "GND_29_1") (pintype "power_in"))
      (node (ref "U2") (pin "29_2") (pinfunction "GND_29_2") (pintype "power_in"))
      (node (ref "U2") (pin "29_3") (pinfunction "GND_29_3") (pintype "power_in"))
      (node (ref "U2") (pin "29_4") (pinfunction "GND_29_4") (pintype "power_in"))
      (node (ref "U2") (pin "29_5") (pinfunction "GND_29_5") (pintype "power_in"))
      (node (ref "U2") (pin "29_6") (pinfunction "GND_29_6") (pintype "power_in"))
      (node (ref "U2") (pin "29_7") (pinfunction "GND_29_7") (pintype "power_in"))
      (node (ref "U2") (pin "29_8") (pinfunction "GND_29_8") (pintype "power_in"))
      (node (ref "U2") (pin "29_9") (pinfunction "GND_29_9") (pintype "power_in"))
      (node (ref "U3") (pin "13") (pinfunction "GND_13") (pintype "power_in"))
      (node (ref "U4") (pin "1") (pinfunction "CTG_1") (pintype "power_in"))
      (node (ref "U4") (pin "4") (pinfunction "GND_4") (pintype "power_in"))
      (node (ref "U4") (pin "6") (pinfunction "QSTRT_6") (pintype "input"))
      (node (ref "U4") (pin "9") (pinfunction "EP_9") (pintype "power_in"))
    )
    (net (code "14") (name "GPIO8") (class "Default")
      (node (ref "R1") (pin "1") (pinfunction "1_1") (pintype "passive"))
      (node (ref "U2") (pin "10") (pinfunction "IO8_10") (pintype "bidirectional"))
    )
    (net (code "15") (name "I2C_PW") (class "Default")
      (node (ref "C1") (pin "1") (pinfunction "1_1") (pintype "passive"))
      (node (ref "C2") (pin "1") (pinfunction "1_1") (pintype "passive"))
      (node (ref "R1_PINH") (pin "2") (pinfunction "2_2") (pintype "passive"))
      (node (ref "R2-PINH") (pin "2") (pinfunction "2_2") (pintype "passive"))
      (node (ref "SENSOR2") (pin "2") (pinfunction "CSB_2") (pintype "input"))
      (node (ref "SENSOR2") (pin "6") (pinfunction "VDDIO_6") (pintype "power_in"))
      (node (ref "SENSOR2") (pin "8") (pinfunction "VDD_8") (pintype "power_in"))
      (node (ref "U2") (pin "17") (pinfunction "IO19_17") (pintype "bidirectional"))
    )
    (net (code "16") (name "INT_RTC") (class "Default")
      (node (ref "R1_PINH1") (pin "1") (pinfunction "1_1") (pintype "passive"))
      (node (ref "TP15") (pin "TP") (pinfunction "TP_TP") (pintype "input"))
      (node (ref "U2") (pin "8") (pinfunction "IO0_8") (pintype "bidirectional"))
      (node (ref "U3") (pin "3") (pinfunction "SQW/~{INT}_3") (pintype "output"))
    )
    (net (code "17") (name "IO{slash}BOOT") (class "Default")
      (node (ref "BOOT_BUTTON") (pin "3") (pinfunction "3_3") (pintype "passive"))
      (node (ref "BOOT_BUTTON") (pin "4") (pinfunction "4_4") (pintype "passive"))
      (node (ref "C6") (pin "1") (pinfunction "1_1") (pintype "passive"))
      (node (ref "R_BOOT") (pin "1") (pinfunction "1_1") (pintype "passive"))
      (node (ref "U2") (pin "15") (pinfunction "IO9_15") (pintype "bidirectional"))
    )
    (net (code "18") (name "IO{slash}CHANGE") (class "Default")
      (node (ref "C10") (pin "1") (pinfunction "1_1") (pintype "passive"))
      (node (ref "CHANGE_BUTTON") (pin "3") (pinfunction "3_3") (pintype "passive"))
      (node (ref "CHANGE_BUTTON") (pin "4") (pinfunction "4_4") (pintype "passive"))
      (node (ref "R_CHANGE") (pin "1") (pinfunction "1_1") (pintype "passive"))
      (node (ref "U2") (pin "23") (pinfunction "IO15_23") (pintype "bidirectional"))
    )
    (net (code "19") (name "MISO") (class "Default")
      (node (ref "D12") (pin "1") (pinfunction "1_1") (pintype "passive"))
      (node (ref "J4") (pin "P7") (pinfunction "DAT0_P7") (pintype "bidirectional"))
      (node (ref "R8") (pin "1") (pinfunction "1_1") (pintype "passive"))
      (node (ref "TP6") (pin "TP") (pinfunction "TP_TP") (pintype "input"))
      (node (ref "U1") (pin "2") (pinfunction "DO(IO1)_2") (pintype "bidirectional"))
      (node (ref "U2") (pin "27") (pinfunction "IO2_27") (pintype "bidirectional"))
    )
    (net (code "20") (name "MOSI") (class "Default")
      (node (ref "D11") (pin "1") (pinfunction "1_1") (pintype "passive"))
      (node (ref "J1") (pin "14") (pinfunction "14_14") (pintype "bidirectional"))
      (node (ref "J4") (pin "P3") (pinfunction "CMD_P3") (pintype "bidirectional"))
      (node (ref "R7") (pin "1") (pinfunction "1_1") (pintype "passive"))
      (node (ref "TP7") (pin "TP") (pinfunction "TP_TP") (pintype "input"))
      (node (ref "U1") (pin "5") (pinfunction "DI(IO0)_5") (pintype "bidirectional"))
      (node (ref "U2") (pin "7") (pinfunction "IO7_7") (pintype "bidirectional"))
    )
    (net (code "21") (name "Net-(CHG_LED-PadC)") (class "Default")
      (node (ref "CHG_LED") (pin "C") (pinfunction "C_C") (pintype "passive"))
      (node (ref "R1_BAT") (pin "1") (pinfunction "1_1") (pintype "passive"))
    )
    (net (code "22") (name "Net-(D2-CATHODE)") (class "Default")
      (node (ref "C1_BAT1") (pin "1") (pinfunction "1_1") (pintype "passive"))
      (node (ref "D2") (pin "1") (pinfunction "CATHODE_1") (pintype "bidirectional"))
      (node (ref "IC4") (pin "1") (pinfunction "VIN_1") (pintype "bidirectional"))
      (node (ref "IC4") (pin "3") (pinfunction "CE_3") (pintype "bidirectional"))
      (node (ref "Q1") (pin "2") (pinfunction "S_2") (pintype "bidirectional"))
    )
    (net (code "23") (name "Net-(D3-A)") (class "Default")
      (node (ref "C4") (pin "1") (pinfunction "1_1") (pintype "passive"))
      (node (ref "D3") (pin "2") (pinfunction "A_2") (pintype "bidirectional"))
      (node (ref "D4") (pin "1") (pinfunction "K_1") (pintype "bidirectional"))
    )
    (net (code "24") (name "Net-(D7-CATHODE)") (class "Default")
      (node (ref "D7") (pin "1") (pinfunction "CATHODE_1") (pintype "bidirectional"))
      (node (ref "R_CAPACITOR") (pin "1") (pinfunction "1_1") (pintype "passive"))
    )
    (net (code "25") (name "Net-(EPD_C1-Pad2)") (class "Default")
      (node (ref "EPD_C1") (pin "2") (pinfunction "2_2") (pintype "passive"))
      (node (ref "J1") (pin "4") (pinfunction "4_4") (pintype "bidirectional"))
    )
    (net (code "26") (name "Net-(EPD_C2-Pad2)") (class "Default")
      (node (ref "EPD_C2") (pin "2") (pinfunction "2_2") (pintype "passive"))
      (node (ref "J1") (pin "5") (pinfunction "5_5") (pintype "bidirectional"))
    )
    (net (code "27") (name "Net-(EPD_C6-Pad2)") (class "Default")
      (node (ref "EPD_C6") (pin "2") (pinfunction "2_2") (pintype "passive"))
      (node (ref "J1") (pin "18") (pinfunction "18_18") (pintype "bidirectional"))
    )
    (net (code "28") (name "Net-(EPD_C7-Pad2)") (class "Default")
      (node (ref "EPD_C7") (pin "2") (pinfunction "2_2") (pintype "passive"))
      (node (ref "J1") (pin "19") (pinfunction "19_19") (pintype "bidirectional"))
    )
    (net (code "29") (name "Net-(EPD_C8-Pad2)") (class "Default")
      (node (ref "EPD_C8") (pin "2") (pinfunction "2_2") (pintype "passive"))
      (node (ref "J1") (pin "20") (pinfunction "20_20") (pintype "bidirectional"))
    )
    (net (code "30") (name "Net-(EPD_C10-Pad2)") (class "Default")
      (node (ref "EPD_C10") (pin "2") (pinfunction "2_2") (pintype "passive"))
      (node (ref "J1") (pin "22") (pinfunction "22_22") (pintype "bidirectional"))
    )
    (net (code "31") (name "Net-(EPD_C12-Pad2)") (class "Default")
      (node (ref "EPD_C12") (pin "2") (pinfunction "2_2") (pintype "passive"))
      (node (ref "J1") (pin "24") (pinfunction "24_24") (pintype "bidirectional"))
    )
    (net (code "32") (name "Net-(IC1-CT)") (class "Default")
      (node (ref "C_DELAY") (pin "1") (pinfunction "1_1") (pintype "passive"))
      (node (ref "IC1") (pin "5") (pinfunction "CT_5") (pintype "bidirectional"))
    )
    (net (code "33") (name "Net-(J2-PadA5)") (class "Default")
      (node (ref "J2") (pin "A5") (pinfunction "A5_A5") (pintype "bidirectional"))
      (node (ref "R2-USB1") (pin "2") (pinfunction "2_2") (pintype "passive"))
    )
    (net (code "34") (name "Net-(J2-PadB5)") (class "Default")
      (node (ref "J2") (pin "B5") (pinfunction "B5_B5") (pintype "bidirectional"))
      (node (ref "R2-USB") (pin "1") (pinfunction "1_1") (pintype "passive"))
    )
    (net (code "35") (name "Net-(MCP73831-PROG)") (class "Default")
      (node (ref "MCP73831") (pin "5") (pinfunction "PROG_5") (pintype "input"))
      (node (ref "R2_BAT") (pin "2") (pinfunction "2_2") (pintype "passive"))
    )
    (net (code "36") (name "Net-(MCP73831-STAT)") (class "Default")
      (node (ref "MCP73831") (pin "1") (pinfunction "STAT_1") (pintype "output"))
      (node (ref "R1_BAT") (pin "2") (pinfunction "2_2") (pintype "passive"))
    )
    (net (code "37") (name "PREVGH") (class "Default")
      (node (ref "D5") (pin "1") (pinfunction "K_1") (pintype "bidirectional"))
      (node (ref "EPD_C9") (pin "2") (pinfunction "2_2") (pintype "passive"))
      (node (ref "J1") (pin "21") (pinfunction "21_21") (pintype "bidirectional"))
    )
    (net (code "38") (name "PREVGL") (class "Default")
      (node (ref "D4") (pin "2") (pinfunction "A_2") (pintype "bidirectional"))
      (node (ref "EPD_C11") (pin "2") (pinfunction "2_2") (pintype "passive"))
      (node (ref "J1") (pin "23") (pinfunction "23_23") (pintype "bidirectional"))
    )
    (net (code "39") (name "RESE") (class "Default")
      (node (ref "J1") (pin "3") (pinfunction "3_3") (pintype "bidirectional"))
      (node (ref "Q3") (pin "2") (pinfunction "S_2") (pintype "bidirectional"))
      (node (ref "R3") (pin "2") (pinfunction "2_2") (pintype "passive"))
    )
    (net (code "40") (name "RESE'") (class "Default")
      (node (ref "R2") (pin "2") (pinfunction "2_2") (pintype "passive"))
      (node (ref "R3") (pin "1") (pinfunction "1_1") (pintype "passive"))
      (node (ref "SJ1") (pin "2") (pinfunction "2_2") (pintype "passive"))
    )
    (net (code "41") (name "RESET") (class "Default")
      (node (ref "C5") (pin "1") (pinfunction "1_1") (pintype "passive"))
      (node (ref "IC1") (pin "1") (pinfunction "VOUT_1") (pintype "bidirectional"))
      (node (ref "RESET_BUTTON") (pin "3") (pinfunction "3_3") (pintype "passive"))
      (node (ref "RESET_BUTTON") (pin "4") (pinfunction "4_4") (pintype "passive"))
      (node (ref "R_RESET") (pin "1") (pinfunction "1_1") (pintype "passive"))
      (node (ref "U2") (pin "3") (pinfunction "EN_3") (pintype "input"))
    )
    (net (code "42") (name "RTC_RST") (class "Default")
      (node (ref "U2") (pin "16") (pinfunction "IO18_16") (pintype "bidirectional"))
      (node (ref "U3") (pin "4") (pinfunction "~{RST}_4") (pintype "input"))
    )
    (net (code "43") (name "RX") (class "Default")
      (node (ref "TP2") (pin "TP") (pinfunction "TP_TP") (pintype "input"))
      (node (ref "U2") (pin "24") (pinfunction "RXD0/GPIO17_24") (pintype "bidirectional"))
    )
    (net (code "44") (name "SCK") (class "Default")
      (node (ref "D10") (pin "1") (pinfunction "1_1") (pintype "passive"))
      (node (ref "J1") (pin "13") (pinfunction "13_13") (pintype "bidirectional"))
      (node (ref "J4") (pin "P5") (pinfunction "CLK_P5") (pintype "bidirectional"))
      (node (ref "R6") (pin "1") (pinfunction "1_1") (pintype "passive"))
      (node (ref "TP8") (pin "TP") (pinfunction "TP_TP") (pintype "input"))
      (node (ref "U1") (pin "6") (pinfunction "CLK_6") (pintype "input"))
      (node (ref "U2") (pin "6") (pinfunction "IO6_6") (pintype "bidirectional"))
    )
    (net (code "45") (name "SCL") (class "Default")
      (node (ref "J3") (pin "4") (pinfunction "4_4") (pintype "passive"))
      (node (ref "R2-PINH") (pin "1") (pinfunction "1_1") (pintype "passive"))
      (node (ref "SENSOR2") (pin "4") (pinfunction "SCK_4") (pintype "input"))
      (node (ref "U2") (pin "20") (pinfunction "IO22_20") (pintype "bidirectional"))
      (node (ref "U3") (pin "16") (pinfunction "SCL_16") (pintype "input"))
      (node (ref "U4") (pin "7") (pinfunction "SCL_7") (pintype "input"))
    )
    (net (code "46") (name "SDA") (class "Default")
      (node (ref "J3") (pin "3") (pinfunction "3_3") (pintype "passive"))
      (node (ref "R1_PINH") (pin "1") (pinfunction "1_1") (pintype "passive"))
      (node (ref "SENSOR2") (pin "3") (pinfunction "SDI_3") (pintype "bidirectional"))
      (node (ref "U2") (pin "19") (pinfunction "IO21_19") (pintype "bidirectional"))
      (node (ref "U3") (pin "15") (pinfunction "SDA_15") (pintype "bidirectional"))
      (node (ref "U4") (pin "8") (pinfunction "SDA_8") (pintype "bidirectional"))
    )
    (net (code "47") (name "SRC") (class "Default")
      (node (ref "C4") (pin "2") (pinfunction "2_2") (pintype "passive"))
      (node (ref "D5") (pin "2") (pinfunction "A_2") (pintype "bidirectional"))
      (node (ref "L1") (pin "1") (pinfunction "1_1") (pintype "passive"))
      (node (ref "Q3") (pin "3") (pinfunction "D_3") (pintype "bidirectional"))
    )
    (net (code "48") (name "SS_SD") (class "Default")
      (node (ref "D8") (pin "1") (pinfunction "1_1") (pintype "passive"))
      (node (ref "J4") (pin "P2") (pinfunction "CD/DAT3_P2") (pintype "bidirectional"))
      (node (ref "R10") (pin "1") (pinfunction "1_1") (pintype "passive"))
      (node (ref "U2") (pin "4") (pinfunction "IO4_4") (pintype "bidirectional"))
    )
    (net (code "49") (name "TX") (class "Default")
      (node (ref "TP1") (pin "TP") (pinfunction "TP_TP") (pintype "input"))
      (node (ref "U2") (pin "25") (pinfunction "TXD0/GPIO16_25") (pintype "bidirectional"))
    )
    (net (code "50") (name "USB_D+") (class "Default")
      (node (ref "D1") (pin "1") (pinfunction "I/O1_1_1") (pintype "bidirectional"))
      (node (ref "U2") (pin "14") (pinfunction "IO13_14") (pintype "bidirectional"))
    )
    (net (code "51") (name "USB_D-") (class "Default")
      (node (ref "D1") (pin "3") (pinfunction "I/O2_1_3") (pintype "bidirectional"))
      (node (ref "U2") (pin "13") (pinfunction "IO12_13") (pintype "bidirectional"))
    )
    (net (code "52") (name "VBAT") (class "Default")
      (node (ref "C2_BAT") (pin "1") (pinfunction "1_1") (pintype "passive"))
      (node (ref "MCP73831") (pin "3") (pinfunction "VBAT_3") (pintype "power_in"))
      (node (ref "Q1") (pin "3") (pinfunction "D_3") (pintype "bidirectional"))
      (node (ref "TP3") (pin "TP") (pinfunction "TP_TP") (pintype "input"))
      (node (ref "U4") (pin "2") (pinfunction "CELL_2") (pintype "power_in"))
      (node (ref "U4") (pin "3") (pinfunction "VDD_3") (pintype "power_in"))
    )
    (net (code "53") (name "VBUS") (class "Default")
      (node (ref "C1_BAT") (pin "1") (pinfunction "1_1") (pintype "passive"))
      (node (ref "C4_USB") (pin "1") (pinfunction "1_1") (pintype "passive"))
      (node (ref "C5_USB") (pin "1") (pinfunction "1_1") (pintype "passive"))
      (node (ref "CHG_LED") (pin "A") (pinfunction "A_A") (pintype "passive"))
      (node (ref "D1") (pin "5") (pinfunction "VBUS_5") (pintype "bidirectional"))
      (node (ref "D2") (pin "2") (pinfunction "ANODE_2") (pintype "bidirectional"))
      (node (ref "MCP73831") (pin "4") (pinfunction "VIN_4") (pintype "power_in"))
      (node (ref "PFMF.050.1") (pin "2") (pinfunction "2_2") (pintype "passive"))
      (node (ref "Q1") (pin "1") (pinfunction "G_1") (pintype "bidirectional"))
      (node (ref "R1_PWRUSB") (pin "2") (pinfunction "2_2") (pintype "passive"))
      (node (ref "TP14") (pin "TP") (pinfunction "TP_TP") (pintype "input"))
    )
    (net (code "54") (name "VRTC") (class "Default")
      (node (ref "C10_SUPERCAP") (pin "2") (pinfunction "2_2") (pintype "passive"))
      (node (ref "C8") (pin "1") (pinfunction "1_1") (pintype "passive"))
      (node (ref "R_CAPACITOR") (pin "2") (pinfunction "2_2") (pintype "passive"))
      (node (ref "U3") (pin "14") (pinfunction "VBAT_14") (pintype "power_in"))
    )
    (net (code "55") (name "VUSB") (class "Default")
      (node (ref "J2") (pin "A4") (pinfunction "A4_A4") (pintype "bidirectional"))
      (node (ref "J2") (pin "A9") (pinfunction "A9_A9") (pintype "bidirectional"))
      (node (ref "J2") (pin "B4") (pinfunction "B4_B4") (pintype "bidirectional"))
      (node (ref "J2") (pin "B9") (pinfunction "B9_B9") (pintype "bidirectional"))
      (node (ref "PFMF.050.1") (pin "1") (pinfunction "1_1") (pintype "passive"))
    )
    (net (code "56") (name "unconnected-(IC1-NC-Pad4)") (class "Default")
      (node (ref "IC1") (pin "4") (pinfunction "NC_4") (pintype "no_connect"))
    )
    (net (code "57") (name "unconnected-(IC4-NC-Pad4)") (class "Default")
      (node (ref "IC4") (pin "4") (pinfunction "NC_4") (pintype "no_connect"))
    )
    (net (code "58") (name "unconnected-(J1-Pad1)") (class "Default")
      (node (ref "J1") (pin "1") (pinfunction "1_1") (pintype "bidirectional"))
    )
    (net (code "59") (name "unconnected-(J1-Pad6)") (class "Default")
      (node (ref "J1") (pin "6") (pinfunction "6_6") (pintype "bidirectional"))
    )
    (net (code "60") (name "unconnected-(J1-Pad7)") (class "Default")
      (node (ref "J1") (pin "7") (pinfunction "7_7") (pintype "bidirectional"))
    )
    (net (code "61") (name "unconnected-(J2-PadA8)") (class "Default")
      (node (ref "J2") (pin "A8") (pinfunction "A8_A8") (pintype "bidirectional"))
    )
    (net (code "62") (name "unconnected-(J2-PadB8)") (class "Default")
      (node (ref "J2") (pin "B8") (pinfunction "B8_B8") (pintype "bidirectional"))
    )
    (net (code "63") (name "unconnected-(J4-DAT1-PadP8)") (class "Default")
      (node (ref "J4") (pin "P8") (pinfunction "DAT1_P8") (pintype "bidirectional"))
    )
    (net (code "64") (name "unconnected-(J4-DAT2-PadP1)") (class "Default")
      (node (ref "J4") (pin "P1") (pinfunction "DAT2_P1") (pintype "bidirectional"))
    )
    (net (code "65") (name "unconnected-(J4-DETECTION_1-PadS1)") (class "Default")
      (node (ref "J4") (pin "S1") (pinfunction "DETECTION_1_S1") (pintype "bidirectional"))
    )
    (net (code "66") (name "unconnected-(J4-DETECTION_2-PadS2)") (class "Default")
      (node (ref "J4") (pin "S2") (pinfunction "DETECTION_2_S2") (pintype "bidirectional"))
    )
    (net (code "67") (name "unconnected-(U2-NC-Pad22)") (class "Default")
      (node (ref "U2") (pin "22") (pinfunction "NC_22") (pintype "no_connect"))
    )
    (net (code "68") (name "unconnected-(U4-~{ALERT}-Pad5)") (class "Default")
      (node (ref "U4") (pin "5") (pinfunction "~{ALERT}_5") (pintype "output"))
    )
  )
)
